# untitled.net
KiCad netlist of a schematic drawn in EAGLE
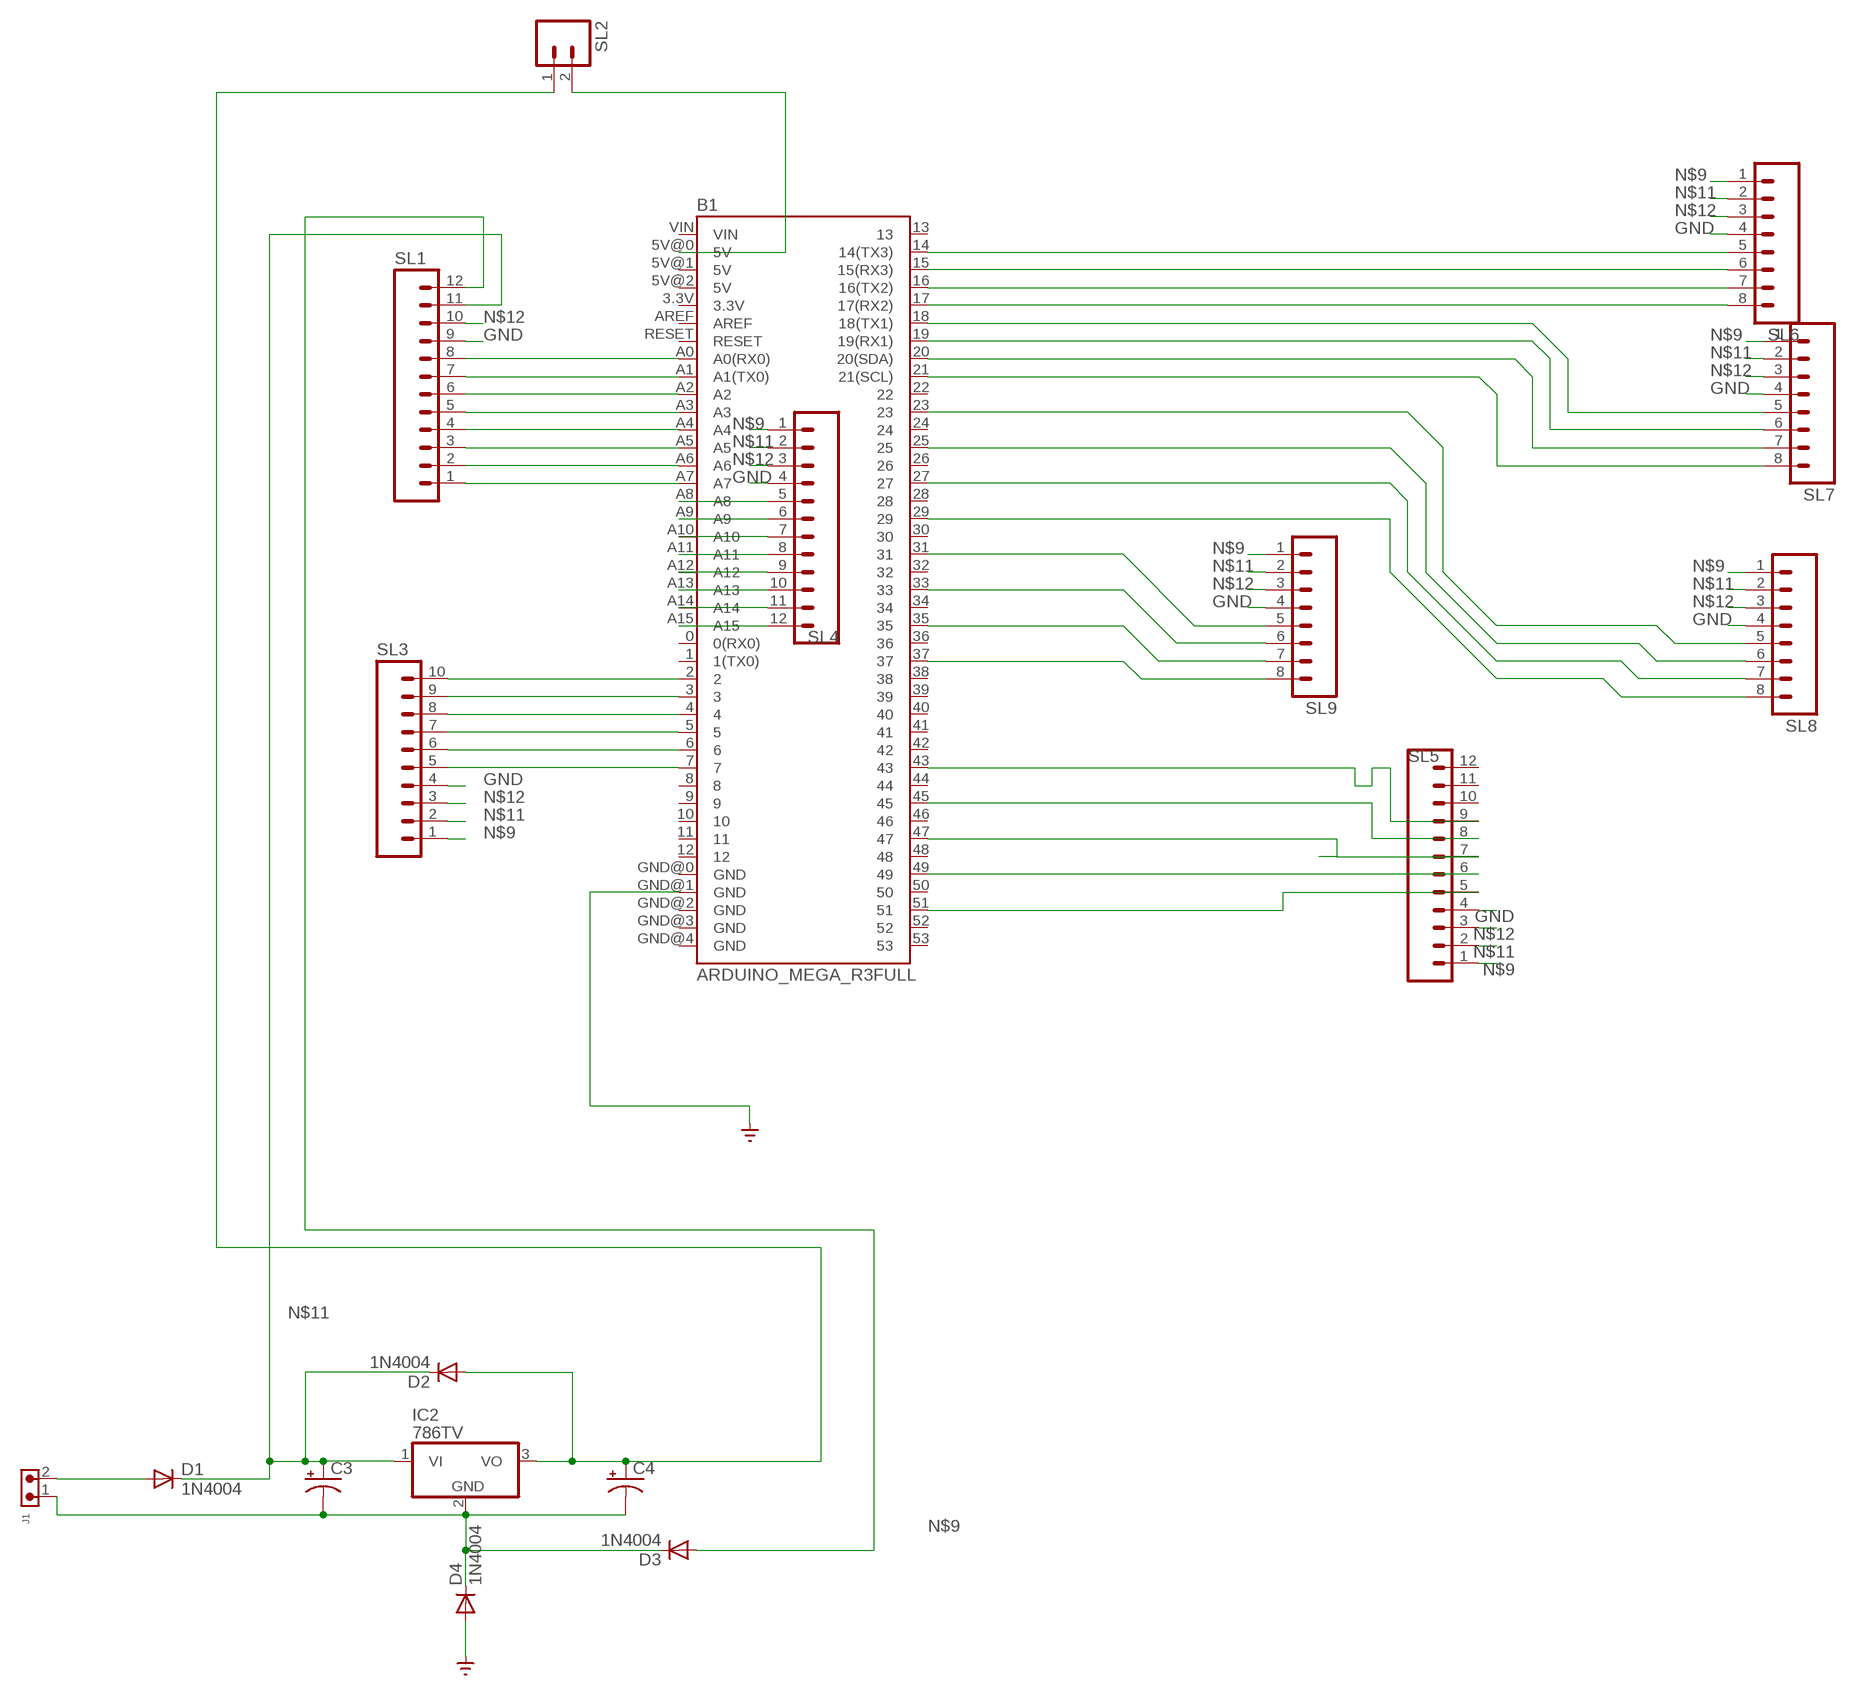
[diagram p0: schematic, sheet 1]

(export (version "E")
  (design (tool "Eeschema 10.0.6"))
  (components
    (comp (ref "B1")
      (value "ARDUINO_MEGA_R3FULL")
      (footprint "eagle-import:ARDUINO_MEGA")
      (libsource (lib "eagle-import") (part "ARDUINO_MEGA_R3FULL"))
    )
    (comp (ref "C3")
      (value "CAPACITOR-PE5-10.5")
      (footprint "eagle-import:E5-10,5")
      (libsource (lib "eagle-import") (part "CAPACITOR-PE5-10.5"))
    )
    (comp (ref "C4")
      (value "CAPACITOR-PE5-6")
      (footprint "eagle-import:E5-6")
      (libsource (lib "eagle-import") (part "CAPACITOR-PE5-6"))
    )
    (comp (ref "D1")
      (value "1N4004")
      (footprint "eagle-import:DO41-10")
      (libsource (lib "eagle-import") (part "1N4004"))
    )
    (comp (ref "D2")
      (value "1N4004")
      (footprint "eagle-import:DO41-10")
      (libsource (lib "eagle-import") (part "1N4004"))
    )
    (comp (ref "D3")
      (value "1N4004")
      (footprint "eagle-import:DO41-10")
      (libsource (lib "eagle-import") (part "1N4004"))
    )
    (comp (ref "D4")
      (value "1N4004")
      (footprint "eagle-import:DO41-10")
      (libsource (lib "eagle-import") (part "1N4004"))
    )
    (comp (ref "IC2")
      (value "786TV")
      (footprint "eagle-import:TO220V")
      (libsource (lib "eagle-import") (part "78TV6"))
    )
    (comp (ref "J1")
      (value "691305530002")
      (footprint "eagle-import:691305530002")
      (libsource (lib "eagle-import") (part "691305530002"))
    )
    (comp (ref "SL1")
      (value "M12")
      (footprint "eagle-import:12P")
      (libsource (lib "eagle-import") (part "M12"))
    )
    (comp (ref "SL2")
      (value "M02")
      (footprint "eagle-import:02P")
      (libsource (lib "eagle-import") (part "M02"))
    )
    (comp (ref "SL3")
      (value "M10")
      (footprint "eagle-import:10P")
      (libsource (lib "eagle-import") (part "M10"))
    )
    (comp (ref "SL4")
      (value "M12")
      (footprint "eagle-import:12P")
      (libsource (lib "eagle-import") (part "M12"))
    )
    (comp (ref "SL5")
      (value "M12")
      (footprint "eagle-import:12P")
      (libsource (lib "eagle-import") (part "M12"))
    )
    (comp (ref "SL6")
      (value "M08")
      (footprint "eagle-import:08P")
      (libsource (lib "eagle-import") (part "M08"))
    )
    (comp (ref "SL7")
      (value "M08")
      (footprint "eagle-import:08P")
      (libsource (lib "eagle-import") (part "M08"))
    )
    (comp (ref "SL8")
      (value "M08")
      (footprint "eagle-import:08P")
      (libsource (lib "eagle-import") (part "M08"))
    )
    (comp (ref "SL9")
      (value "M08")
      (footprint "eagle-import:08P")
      (libsource (lib "eagle-import") (part "M08"))
    )
  )
  (nets
    (net (code "1") (name "/N$9") (class "Default")
      (node (ref "D3") (pin "A") (pinfunction "A_A") (pintype "passive"))
      (node (ref "SL1") (pin "12") (pinfunction "12_12") (pintype "passive"))
      (node (ref "SL3") (pin "1") (pinfunction "1_1") (pintype "passive"))
      (node (ref "SL4") (pin "1") (pinfunction "1_1") (pintype "passive"))
      (node (ref "SL5") (pin "1") (pinfunction "1_1") (pintype "passive"))
      (node (ref "SL6") (pin "1") (pinfunction "1_1") (pintype "passive"))
      (node (ref "SL7") (pin "1") (pinfunction "1_1") (pintype "passive"))
      (node (ref "SL8") (pin "1") (pinfunction "1_1") (pintype "passive"))
      (node (ref "SL9") (pin "1") (pinfunction "1_1") (pintype "passive"))
    )
    (net (code "2") (name "/N$11") (class "Default")
      (node (ref "C3") (pin "+") (pinfunction "+_+") (pintype "passive"))
      (node (ref "D1") (pin "C") (pinfunction "C_C") (pintype "passive"))
      (node (ref "D2") (pin "C") (pinfunction "C_C") (pintype "passive"))
      (node (ref "IC2") (pin "1") (pinfunction "VI_1") (pintype "input"))
      (node (ref "SL1") (pin "11") (pinfunction "11_11") (pintype "passive"))
      (node (ref "SL3") (pin "2") (pinfunction "2_2") (pintype "passive"))
      (node (ref "SL4") (pin "2") (pinfunction "2_2") (pintype "passive"))
      (node (ref "SL5") (pin "2") (pinfunction "2_2") (pintype "passive"))
      (node (ref "SL6") (pin "2") (pinfunction "2_2") (pintype "passive"))
      (node (ref "SL7") (pin "2") (pinfunction "2_2") (pintype "passive"))
      (node (ref "SL8") (pin "2") (pinfunction "2_2") (pintype "passive"))
      (node (ref "SL9") (pin "2") (pinfunction "2_2") (pintype "passive"))
    )
    (net (code "3") (name "/N$12") (class "Default")
      (node (ref "C4") (pin "+") (pinfunction "+_+") (pintype "passive"))
      (node (ref "D2") (pin "A") (pinfunction "A_A") (pintype "passive"))
      (node (ref "IC2") (pin "3") (pinfunction "VO_3") (pintype "passive"))
      (node (ref "SL1") (pin "10") (pinfunction "10_10") (pintype "passive"))
      (node (ref "SL2") (pin "1") (pinfunction "1_1") (pintype "passive"))
      (node (ref "SL3") (pin "3") (pinfunction "3_3") (pintype "passive"))
      (node (ref "SL4") (pin "3") (pinfunction "3_3") (pintype "passive"))
      (node (ref "SL5") (pin "3") (pinfunction "3_3") (pintype "passive"))
      (node (ref "SL6") (pin "3") (pinfunction "3_3") (pintype "passive"))
      (node (ref "SL7") (pin "3") (pinfunction "3_3") (pintype "passive"))
      (node (ref "SL8") (pin "3") (pinfunction "3_3") (pintype "passive"))
      (node (ref "SL9") (pin "3") (pinfunction "3_3") (pintype "passive"))
    )
    (net (code "4") (name "Net-(B1-5V-Pad5V@0)") (class "Default")
      (node (ref "B1") (pin "5V@0") (pinfunction "5V_5V@0") (pintype "bidirectional"))
      (node (ref "SL2") (pin "2") (pinfunction "2_2") (pintype "passive"))
    )
    (net (code "5") (name "Net-(B1-14(TX3))") (class "Default")
      (node (ref "B1") (pin "14") (pinfunction "14(TX3)_14") (pintype "bidirectional"))
      (node (ref "SL6") (pin "5") (pinfunction "5_5") (pintype "passive"))
    )
    (net (code "6") (name "Net-(B1-15(RX3))") (class "Default")
      (node (ref "B1") (pin "15") (pinfunction "15(RX3)_15") (pintype "bidirectional"))
      (node (ref "SL6") (pin "6") (pinfunction "6_6") (pintype "passive"))
    )
    (net (code "7") (name "Net-(B1-16(TX2))") (class "Default")
      (node (ref "B1") (pin "16") (pinfunction "16(TX2)_16") (pintype "bidirectional"))
      (node (ref "SL6") (pin "7") (pinfunction "7_7") (pintype "passive"))
    )
    (net (code "8") (name "Net-(B1-17(RX2))") (class "Default")
      (node (ref "B1") (pin "17") (pinfunction "17(RX2)_17") (pintype "bidirectional"))
      (node (ref "SL6") (pin "8") (pinfunction "8_8") (pintype "passive"))
    )
    (net (code "9") (name "Net-(B1-18(TX1))") (class "Default")
      (node (ref "B1") (pin "18") (pinfunction "18(TX1)_18") (pintype "bidirectional"))
      (node (ref "SL7") (pin "5") (pinfunction "5_5") (pintype "passive"))
    )
    (net (code "10") (name "Net-(B1-19(RX1))") (class "Default")
      (node (ref "B1") (pin "19") (pinfunction "19(RX1)_19") (pintype "bidirectional"))
      (node (ref "SL7") (pin "6") (pinfunction "6_6") (pintype "passive"))
    )
    (net (code "11") (name "Net-(B1-20(SDA))") (class "Default")
      (node (ref "B1") (pin "20") (pinfunction "20(SDA)_20") (pintype "bidirectional"))
      (node (ref "SL7") (pin "7") (pinfunction "7_7") (pintype "passive"))
    )
    (net (code "12") (name "Net-(B1-21(SCL))") (class "Default")
      (node (ref "B1") (pin "21") (pinfunction "21(SCL)_21") (pintype "bidirectional"))
      (node (ref "SL7") (pin "8") (pinfunction "8_8") (pintype "passive"))
    )
    (net (code "13") (name "Net-(B1-A0(RX0))") (class "Default")
      (node (ref "B1") (pin "A0") (pinfunction "A0(RX0)_A0") (pintype "bidirectional"))
      (node (ref "SL1") (pin "8") (pinfunction "8_8") (pintype "passive"))
    )
    (net (code "14") (name "Net-(B1-A1(TX0))") (class "Default")
      (node (ref "B1") (pin "A1") (pinfunction "A1(TX0)_A1") (pintype "bidirectional"))
      (node (ref "SL1") (pin "7") (pinfunction "7_7") (pintype "passive"))
    )
    (net (code "15") (name "Net-(B1-Pad2)") (class "Default")
      (node (ref "B1") (pin "2") (pinfunction "2_2") (pintype "bidirectional"))
      (node (ref "SL3") (pin "10") (pinfunction "10_10") (pintype "passive"))
    )
    (net (code "16") (name "Net-(B1-Pad3)") (class "Default")
      (node (ref "B1") (pin "3") (pinfunction "3_3") (pintype "bidirectional"))
      (node (ref "SL3") (pin "9") (pinfunction "9_9") (pintype "passive"))
    )
    (net (code "17") (name "Net-(B1-Pad4)") (class "Default")
      (node (ref "B1") (pin "4") (pinfunction "4_4") (pintype "bidirectional"))
      (node (ref "SL3") (pin "8") (pinfunction "8_8") (pintype "passive"))
    )
    (net (code "18") (name "Net-(B1-Pad5)") (class "Default")
      (node (ref "B1") (pin "5") (pinfunction "5_5") (pintype "bidirectional"))
      (node (ref "SL3") (pin "7") (pinfunction "7_7") (pintype "passive"))
    )
    (net (code "19") (name "Net-(B1-Pad6)") (class "Default")
      (node (ref "B1") (pin "6") (pinfunction "6_6") (pintype "bidirectional"))
      (node (ref "SL3") (pin "6") (pinfunction "6_6") (pintype "passive"))
    )
    (net (code "20") (name "Net-(B1-Pad7)") (class "Default")
      (node (ref "B1") (pin "7") (pinfunction "7_7") (pintype "bidirectional"))
      (node (ref "SL3") (pin "5") (pinfunction "5_5") (pintype "passive"))
    )
    (net (code "21") (name "Net-(B1-Pad23)") (class "Default")
      (node (ref "B1") (pin "23") (pinfunction "23_23") (pintype "bidirectional"))
      (node (ref "SL8") (pin "5") (pinfunction "5_5") (pintype "passive"))
    )
    (net (code "22") (name "Net-(B1-Pad25)") (class "Default")
      (node (ref "B1") (pin "25") (pinfunction "25_25") (pintype "bidirectional"))
      (node (ref "SL8") (pin "6") (pinfunction "6_6") (pintype "passive"))
    )
    (net (code "23") (name "Net-(B1-Pad27)") (class "Default")
      (node (ref "B1") (pin "27") (pinfunction "27_27") (pintype "bidirectional"))
      (node (ref "SL8") (pin "7") (pinfunction "7_7") (pintype "passive"))
    )
    (net (code "24") (name "Net-(B1-Pad29)") (class "Default")
      (node (ref "B1") (pin "29") (pinfunction "29_29") (pintype "bidirectional"))
      (node (ref "SL8") (pin "8") (pinfunction "8_8") (pintype "passive"))
    )
    (net (code "25") (name "Net-(B1-Pad31)") (class "Default")
      (node (ref "B1") (pin "31") (pinfunction "31_31") (pintype "bidirectional"))
      (node (ref "SL9") (pin "5") (pinfunction "5_5") (pintype "passive"))
    )
    (net (code "26") (name "Net-(B1-Pad33)") (class "Default")
      (node (ref "B1") (pin "33") (pinfunction "33_33") (pintype "bidirectional"))
      (node (ref "SL9") (pin "6") (pinfunction "6_6") (pintype "passive"))
    )
    (net (code "27") (name "Net-(B1-Pad35)") (class "Default")
      (node (ref "B1") (pin "35") (pinfunction "35_35") (pintype "bidirectional"))
      (node (ref "SL9") (pin "7") (pinfunction "7_7") (pintype "passive"))
    )
    (net (code "28") (name "Net-(B1-Pad37)") (class "Default")
      (node (ref "B1") (pin "37") (pinfunction "37_37") (pintype "bidirectional"))
      (node (ref "SL9") (pin "8") (pinfunction "8_8") (pintype "passive"))
    )
    (net (code "29") (name "Net-(B1-Pad43)") (class "Default")
      (node (ref "B1") (pin "43") (pinfunction "43_43") (pintype "bidirectional"))
      (node (ref "SL5") (pin "9") (pinfunction "9_9") (pintype "passive"))
    )
    (net (code "30") (name "Net-(B1-Pad45)") (class "Default")
      (node (ref "B1") (pin "45") (pinfunction "45_45") (pintype "bidirectional"))
      (node (ref "SL5") (pin "8") (pinfunction "8_8") (pintype "passive"))
    )
    (net (code "31") (name "Net-(B1-Pad47)") (class "Default")
      (node (ref "B1") (pin "47") (pinfunction "47_47") (pintype "bidirectional"))
      (node (ref "SL5") (pin "7") (pinfunction "7_7") (pintype "passive"))
    )
    (net (code "32") (name "Net-(B1-Pad49)") (class "Default")
      (node (ref "B1") (pin "49") (pinfunction "49_49") (pintype "bidirectional"))
      (node (ref "SL5") (pin "6") (pinfunction "6_6") (pintype "passive"))
    )
    (net (code "33") (name "Net-(B1-Pad51)") (class "Default")
      (node (ref "B1") (pin "51") (pinfunction "51_51") (pintype "bidirectional"))
      (node (ref "SL5") (pin "5") (pinfunction "5_5") (pintype "passive"))
    )
    (net (code "34") (name "Net-(B1-PadA2)") (class "Default")
      (node (ref "B1") (pin "A2") (pinfunction "A2_A2") (pintype "bidirectional"))
      (node (ref "SL1") (pin "6") (pinfunction "6_6") (pintype "passive"))
    )
    (net (code "35") (name "Net-(B1-PadA3)") (class "Default")
      (node (ref "B1") (pin "A3") (pinfunction "A3_A3") (pintype "bidirectional"))
      (node (ref "SL1") (pin "5") (pinfunction "5_5") (pintype "passive"))
    )
    (net (code "36") (name "Net-(B1-PadA4)") (class "Default")
      (node (ref "B1") (pin "A4") (pinfunction "A4_A4") (pintype "bidirectional"))
      (node (ref "SL1") (pin "4") (pinfunction "4_4") (pintype "passive"))
    )
    (net (code "37") (name "Net-(B1-PadA5)") (class "Default")
      (node (ref "B1") (pin "A5") (pinfunction "A5_A5") (pintype "bidirectional"))
      (node (ref "SL1") (pin "3") (pinfunction "3_3") (pintype "passive"))
    )
    (net (code "38") (name "Net-(B1-PadA6)") (class "Default")
      (node (ref "B1") (pin "A6") (pinfunction "A6_A6") (pintype "bidirectional"))
      (node (ref "SL1") (pin "2") (pinfunction "2_2") (pintype "passive"))
    )
    (net (code "39") (name "Net-(B1-PadA7)") (class "Default")
      (node (ref "B1") (pin "A7") (pinfunction "A7_A7") (pintype "bidirectional"))
      (node (ref "SL1") (pin "1") (pinfunction "1_1") (pintype "passive"))
    )
    (net (code "40") (name "Net-(B1-PadA8)") (class "Default")
      (node (ref "B1") (pin "A8") (pinfunction "A8_A8") (pintype "bidirectional"))
      (node (ref "SL4") (pin "5") (pinfunction "5_5") (pintype "passive"))
    )
    (net (code "41") (name "Net-(B1-PadA9)") (class "Default")
      (node (ref "B1") (pin "A9") (pinfunction "A9_A9") (pintype "bidirectional"))
      (node (ref "SL4") (pin "6") (pinfunction "6_6") (pintype "passive"))
    )
    (net (code "42") (name "Net-(B1-PadA10)") (class "Default")
      (node (ref "B1") (pin "A10") (pinfunction "A10_A10") (pintype "bidirectional"))
      (node (ref "SL4") (pin "7") (pinfunction "7_7") (pintype "passive"))
    )
    (net (code "43") (name "Net-(B1-PadA11)") (class "Default")
      (node (ref "B1") (pin "A11") (pinfunction "A11_A11") (pintype "bidirectional"))
      (node (ref "SL4") (pin "8") (pinfunction "8_8") (pintype "passive"))
    )
    (net (code "44") (name "Net-(B1-PadA12)") (class "Default")
      (node (ref "B1") (pin "A12") (pinfunction "A12_A12") (pintype "bidirectional"))
      (node (ref "SL4") (pin "9") (pinfunction "9_9") (pintype "passive"))
    )
    (net (code "45") (name "Net-(B1-PadA13)") (class "Default")
      (node (ref "B1") (pin "A13") (pinfunction "A13_A13") (pintype "bidirectional"))
      (node (ref "SL4") (pin "10") (pinfunction "10_10") (pintype "passive"))
    )
    (net (code "46") (name "Net-(B1-PadA14)") (class "Default")
      (node (ref "B1") (pin "A14") (pinfunction "A14_A14") (pintype "bidirectional"))
      (node (ref "SL4") (pin "11") (pinfunction "11_11") (pintype "passive"))
    )
    (net (code "47") (name "Net-(B1-PadA15)") (class "Default")
      (node (ref "B1") (pin "A15") (pinfunction "A15_A15") (pintype "bidirectional"))
      (node (ref "SL4") (pin "12") (pinfunction "12_12") (pintype "passive"))
    )
    (net (code "48") (name "Net-(D1-PadA)") (class "Default")
      (node (ref "D1") (pin "A") (pinfunction "A_A") (pintype "passive"))
      (node (ref "J1") (pin "2") (pinfunction "2_2") (pintype "passive"))
    )
    (net (code "49") (name "Net-(IC2-GND)") (class "Default")
      (node (ref "C3") (pin "-") (pinfunction "-_-") (pintype "passive"))
      (node (ref "C4") (pin "-") (pinfunction "-_-") (pintype "passive"))
      (node (ref "D3") (pin "C") (pinfunction "C_C") (pintype "passive"))
      (node (ref "D4") (pin "C") (pinfunction "C_C") (pintype "passive"))
      (node (ref "IC2") (pin "2") (pinfunction "GND_2") (pintype "passive"))
      (node (ref "J1") (pin "1") (pinfunction "1_1") (pintype "passive"))
    )
    (net (code "50") (name "SUPPLY_BRASTAN_GND_") (class "Default")
      (node (ref "B1") (pin "GND@1") (pinfunction "GND_GND@1") (pintype "bidirectional"))
      (node (ref "D4") (pin "A") (pinfunction "A_A") (pintype "passive"))
      (node (ref "SL1") (pin "9") (pinfunction "9_9") (pintype "passive"))
      (node (ref "SL3") (pin "4") (pinfunction "4_4") (pintype "passive"))
      (node (ref "SL4") (pin "4") (pinfunction "4_4") (pintype "passive"))
      (node (ref "SL5") (pin "4") (pinfunction "4_4") (pintype "passive"))
      (node (ref "SL6") (pin "4") (pinfunction "4_4") (pintype "passive"))
      (node (ref "SL7") (pin "4") (pinfunction "4_4") (pintype "passive"))
      (node (ref "SL8") (pin "4") (pinfunction "4_4") (pintype "passive"))
      (node (ref "SL9") (pin "4") (pinfunction "4_4") (pintype "passive"))
    )
    (net (code "51") (name "unconnected-(B1-0(RX0)-Pad0)") (class "Default")
      (node (ref "B1") (pin "0") (pinfunction "0(RX0)_0") (pintype "bidirectional"))
    )
    (net (code "52") (name "unconnected-(B1-1(TX0)-Pad1)") (class "Default")
      (node (ref "B1") (pin "1") (pinfunction "1(TX0)_1") (pintype "bidirectional"))
    )
    (net (code "53") (name "unconnected-(B1-5V-Pad5V@1)") (class "Default")
      (node (ref "B1") (pin "5V@1") (pinfunction "5V_5V@1") (pintype "bidirectional"))
    )
    (net (code "54") (name "unconnected-(B1-5V-Pad5V@2)") (class "Default")
      (node (ref "B1") (pin "5V@2") (pinfunction "5V_5V@2") (pintype "bidirectional"))
    )
    (net (code "55") (name "unconnected-(B1-GND-PadGND@0)") (class "Default")
      (node (ref "B1") (pin "GND@0") (pinfunction "GND_GND@0") (pintype "bidirectional"))
    )
    (net (code "56") (name "unconnected-(B1-GND-PadGND@2)") (class "Default")
      (node (ref "B1") (pin "GND@2") (pinfunction "GND_GND@2") (pintype "bidirectional"))
    )
    (net (code "57") (name "unconnected-(B1-GND-PadGND@3)") (class "Default")
      (node (ref "B1") (pin "GND@3") (pinfunction "GND_GND@3") (pintype "bidirectional"))
    )
    (net (code "58") (name "unconnected-(B1-GND-PadGND@4)") (class "Default")
      (node (ref "B1") (pin "GND@4") (pinfunction "GND_GND@4") (pintype "bidirectional"))
    )
    (net (code "59") (name "unconnected-(B1-Pad3.3V)") (class "Default")
      (node (ref "B1") (pin "3.3V") (pinfunction "3.3V_3.3V") (pintype "bidirectional"))
    )
    (net (code "60") (name "unconnected-(B1-Pad8)") (class "Default")
      (node (ref "B1") (pin "8") (pinfunction "8_8") (pintype "bidirectional"))
    )
    (net (code "61") (name "unconnected-(B1-Pad9)") (class "Default")
      (node (ref "B1") (pin "9") (pinfunction "9_9") (pintype "bidirectional"))
    )
    (net (code "62") (name "unconnected-(B1-Pad10)") (class "Default")
      (node (ref "B1") (pin "10") (pinfunction "10_10") (pintype "bidirectional"))
    )
    (net (code "63") (name "unconnected-(B1-Pad11)") (class "Default")
      (node (ref "B1") (pin "11") (pinfunction "11_11") (pintype "bidirectional"))
    )
    (net (code "64") (name "unconnected-(B1-Pad12)") (class "Default")
      (node (ref "B1") (pin "12") (pinfunction "12_12") (pintype "bidirectional"))
    )
    (net (code "65") (name "unconnected-(B1-Pad13)") (class "Default")
      (node (ref "B1") (pin "13") (pinfunction "13_13") (pintype "bidirectional"))
    )
    (net (code "66") (name "unconnected-(B1-Pad22)") (class "Default")
      (node (ref "B1") (pin "22") (pinfunction "22_22") (pintype "bidirectional"))
    )
    (net (code "67") (name "unconnected-(B1-Pad24)") (class "Default")
      (node (ref "B1") (pin "24") (pinfunction "24_24") (pintype "bidirectional"))
    )
    (net (code "68") (name "unconnected-(B1-Pad26)") (class "Default")
      (node (ref "B1") (pin "26") (pinfunction "26_26") (pintype "bidirectional"))
    )
    (net (code "69") (name "unconnected-(B1-Pad28)") (class "Default")
      (node (ref "B1") (pin "28") (pinfunction "28_28") (pintype "bidirectional"))
    )
    (net (code "70") (name "unconnected-(B1-Pad30)") (class "Default")
      (node (ref "B1") (pin "30") (pinfunction "30_30") (pintype "bidirectional"))
    )
    (net (code "71") (name "unconnected-(B1-Pad32)") (class "Default")
      (node (ref "B1") (pin "32") (pinfunction "32_32") (pintype "bidirectional"))
    )
    (net (code "72") (name "unconnected-(B1-Pad34)") (class "Default")
      (node (ref "B1") (pin "34") (pinfunction "34_34") (pintype "bidirectional"))
    )
    (net (code "73") (name "unconnected-(B1-Pad36)") (class "Default")
      (node (ref "B1") (pin "36") (pinfunction "36_36") (pintype "bidirectional"))
    )
    (net (code "74") (name "unconnected-(B1-Pad38)") (class "Default")
      (node (ref "B1") (pin "38") (pinfunction "38_38") (pintype "bidirectional"))
    )
    (net (code "75") (name "unconnected-(B1-Pad39)") (class "Default")
      (node (ref "B1") (pin "39") (pinfunction "39_39") (pintype "bidirectional"))
    )
    (net (code "76") (name "unconnected-(B1-Pad40)") (class "Default")
      (node (ref "B1") (pin "40") (pinfunction "40_40") (pintype "bidirectional"))
    )
    (net (code "77") (name "unconnected-(B1-Pad41)") (class "Default")
      (node (ref "B1") (pin "41") (pinfunction "41_41") (pintype "bidirectional"))
    )
    (net (code "78") (name "unconnected-(B1-Pad42)") (class "Default")
      (node (ref "B1") (pin "42") (pinfunction "42_42") (pintype "bidirectional"))
    )
    (net (code "79") (name "unconnected-(B1-Pad44)") (class "Default")
      (node (ref "B1") (pin "44") (pinfunction "44_44") (pintype "bidirectional"))
    )
    (net (code "80") (name "unconnected-(B1-Pad46)") (class "Default")
      (node (ref "B1") (pin "46") (pinfunction "46_46") (pintype "bidirectional"))
    )
    (net (code "81") (name "unconnected-(B1-Pad48)") (class "Default")
      (node (ref "B1") (pin "48") (pinfunction "48_48") (pintype "bidirectional"))
    )
    (net (code "82") (name "unconnected-(B1-Pad50)") (class "Default")
      (node (ref "B1") (pin "50") (pinfunction "50_50") (pintype "bidirectional"))
    )
    (net (code "83") (name "unconnected-(B1-Pad52)") (class "Default")
      (node (ref "B1") (pin "52") (pinfunction "52_52") (pintype "bidirectional"))
    )
    (net (code "84") (name "unconnected-(B1-Pad53)") (class "Default")
      (node (ref "B1") (pin "53") (pinfunction "53_53") (pintype "bidirectional"))
    )
    (net (code "85") (name "unconnected-(B1-PadAREF)") (class "Default")
      (node (ref "B1") (pin "AREF") (pinfunction "AREF_AREF") (pintype "bidirectional"))
    )
    (net (code "86") (name "unconnected-(B1-PadRESET)") (class "Default")
      (node (ref "B1") (pin "RESET") (pinfunction "RESET_RESET") (pintype "bidirectional"))
    )
    (net (code "87") (name "unconnected-(B1-PadVIN)") (class "Default")
      (node (ref "B1") (pin "VIN") (pinfunction "VIN_VIN") (pintype "bidirectional"))
    )
    (net (code "88") (name "unconnected-(SL5-Pad10)") (class "Default")
      (node (ref "SL5") (pin "10") (pinfunction "10_10") (pintype "passive"))
    )
    (net (code "89") (name "unconnected-(SL5-Pad11)") (class "Default")
      (node (ref "SL5") (pin "11") (pinfunction "11_11") (pintype "passive"))
    )
    (net (code "90") (name "unconnected-(SL5-Pad12)") (class "Default")
      (node (ref "SL5") (pin "12") (pinfunction "12_12") (pintype "passive"))
    )
  )
)
